# Sheet2.net
KiCad netlist of a schematic drawn in Altium Designer
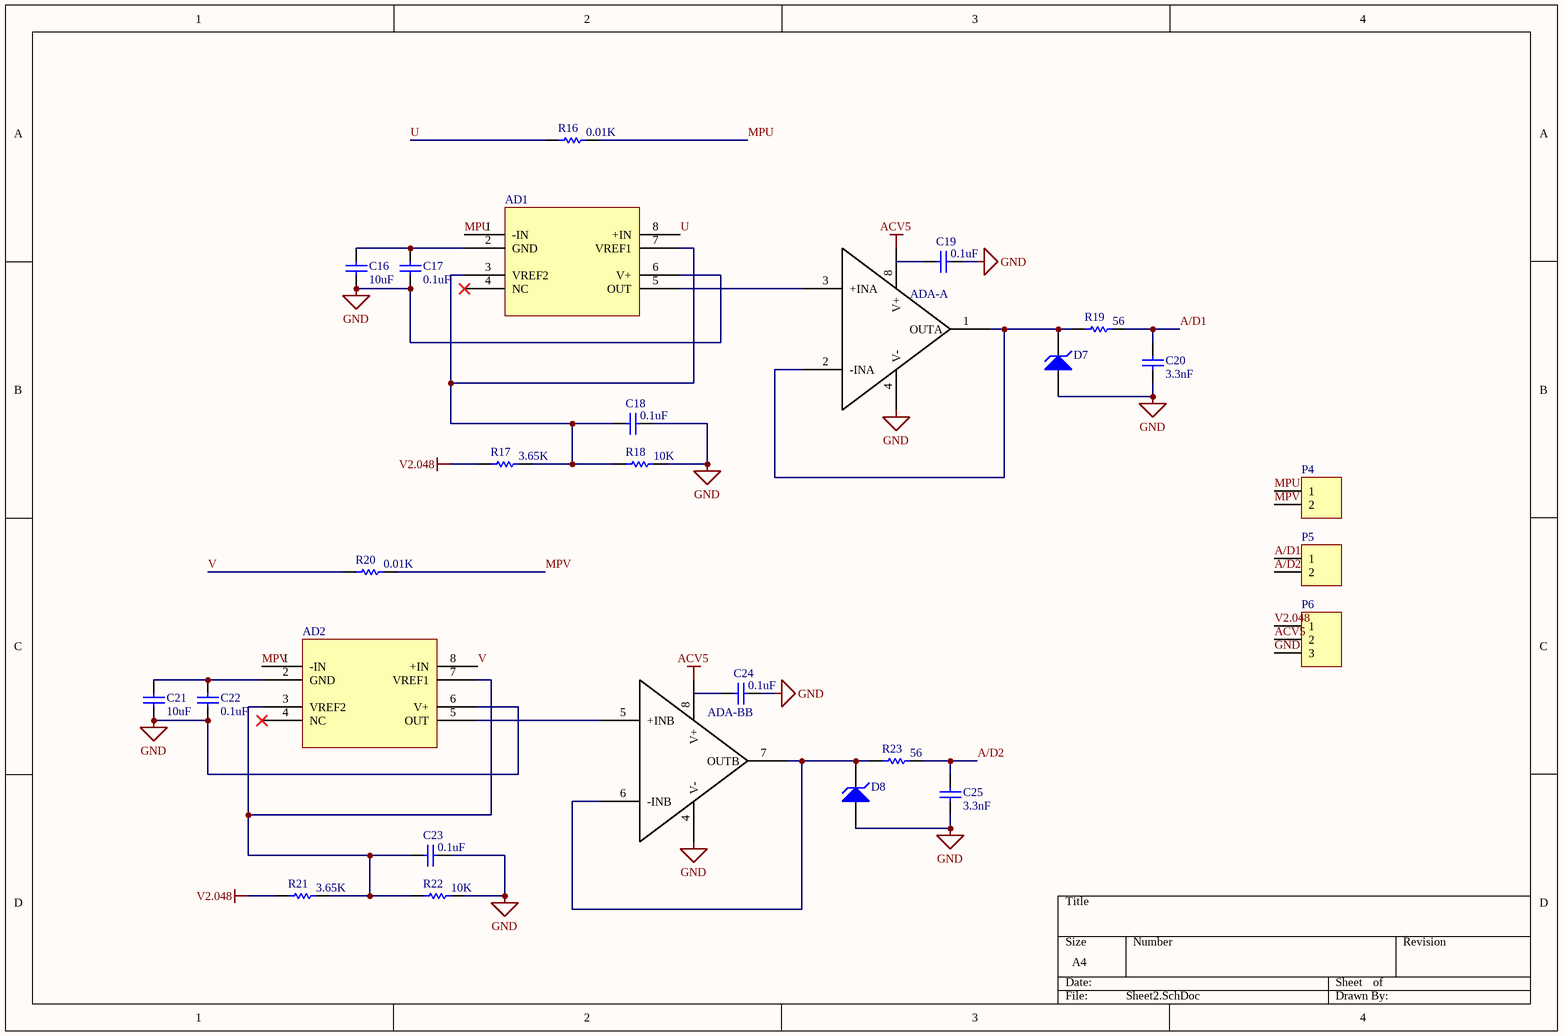
[diagram p0: Sheet2.SchDoc]

(export (version "E")
  (design (tool "Eeschema 10.0.6"))
  (components
    (comp (ref "AD1") (value "AD8210") (footprint "AD8210") (libsource (lib "AD8210") (part "Component_1")))
    (comp (ref "AD2") (value "AD8210") (footprint "AD8210") (libsource (lib "AD8210") (part "Component_1")))
    (comp (ref "ADA-")
      (value "Component_1")
      (footprint "ADA4096")
      (libsource (lib "ADA4096") (part "Component_1"))
    )
    (comp (ref "ADA-B")
      (value "ADA-B")
      (footprint "ADA4096")
      (libsource (lib "ADA4096") (part "Component_1"))
    )
    (comp (ref "C16")
      (value "10uF")
      (footprint "6-0805_M")
      (description "Capacitor")
      (fields (field (name "Comment") "Cap") (field (name "PUBLISHER") "Altium Limited"))
      (libsource (lib "Miscellaneous Devices") (part "Cap"))
    )
    (comp (ref "C17")
      (value "0.1uF")
      (footprint "6-0805_M")
      (description "Capacitor")
      (fields (field (name "Comment") "Cap") (field (name "PUBLISHER") "Altium Limited"))
      (libsource (lib "Miscellaneous Devices") (part "Cap"))
    )
    (comp (ref "C18")
      (value "0.1uF")
      (footprint "6-0805_M")
      (description "Capacitor")
      (fields (field (name "Comment") "Cap") (field (name "PUBLISHER") "Altium Limited"))
      (libsource (lib "Miscellaneous Devices") (part "Cap"))
    )
    (comp (ref "C19")
      (value "0.1uF")
      (footprint "6-0805_M")
      (description "Capacitor")
      (fields (field (name "Comment") "Cap") (field (name "PUBLISHER") "Altium Limited"))
      (libsource (lib "Miscellaneous Devices") (part "Cap"))
    )
    (comp (ref "C20")
      (value "3.3nF")
      (footprint "6-0805_M")
      (description "Capacitor")
      (fields (field (name "Comment") "Cap") (field (name "PUBLISHER") "Altium Limited"))
      (libsource (lib "Miscellaneous Devices") (part "Cap"))
    )
    (comp (ref "C21")
      (value "10uF")
      (footprint "6-0805_M")
      (description "Capacitor")
      (fields (field (name "Comment") "Cap") (field (name "PUBLISHER") "Altium Limited"))
      (libsource (lib "Miscellaneous Devices") (part "Cap"))
    )
    (comp (ref "C22")
      (value "0.1uF")
      (footprint "6-0805_M")
      (description "Capacitor")
      (fields (field (name "Comment") "Cap") (field (name "PUBLISHER") "Altium Limited"))
      (libsource (lib "Miscellaneous Devices") (part "Cap"))
    )
    (comp (ref "C23")
      (value "0.1uF")
      (footprint "6-0805_M")
      (description "Capacitor")
      (fields (field (name "Comment") "Cap") (field (name "PUBLISHER") "Altium Limited"))
      (libsource (lib "Miscellaneous Devices") (part "Cap"))
    )
    (comp (ref "C24")
      (value "0.1uF")
      (footprint "6-0805_M")
      (description "Capacitor")
      (fields (field (name "Comment") "Cap") (field (name "PUBLISHER") "Altium Limited"))
      (libsource (lib "Miscellaneous Devices") (part "Cap"))
    )
    (comp (ref "C25")
      (value "3.3nF")
      (footprint "6-0805_M")
      (description "Capacitor")
      (fields (field (name "Comment") "Cap") (field (name "PUBLISHER") "Altium Limited"))
      (libsource (lib "Miscellaneous Devices") (part "Cap"))
    )
    (comp (ref "D7")
      (value "D Zener")
      (footprint "12Z-2010")
      (description "Zener Diode")
      (fields (field (name "PUBLISHER") "Altium Limited"))
      (libsource (lib "Miscellaneous Devices") (part "D Zener"))
    )
    (comp (ref "D8")
      (value "D Zener")
      (footprint "12Z-2010")
      (description "Zener Diode")
      (fields (field (name "PUBLISHER") "Altium Limited"))
      (libsource (lib "Miscellaneous Devices") (part "D Zener"))
    )
    (comp (ref "P4")
      (value "Header 2")
      (footprint "HDR1X2")
      (description "Header, 2-Pin")
      (fields (field (name "PUBLISHER") "Altium Limited"))
      (libsource (lib "Miscellaneous Connectors") (part "Header 2"))
    )
    (comp (ref "P5")
      (value "Header 2")
      (footprint "HDR1X2")
      (description "Header, 2-Pin")
      (fields (field (name "PUBLISHER") "Altium Limited"))
      (libsource (lib "Miscellaneous Connectors") (part "Header 2"))
    )
    (comp (ref "P6")
      (value "Header 3")
      (footprint "HDR1X3")
      (description "Header, 3-Pin")
      (fields (field (name "PUBLISHER") "Altium Limited"))
      (libsource (lib "Miscellaneous Connectors") (part "Header 3"))
    )
    (comp (ref "R16")
      (value "0.01K")
      (footprint "6-0805_M")
      (description "Resistor")
      (fields (field (name "Comment") "Res1") (field (name "PUBLISHER") "Altium Limited"))
      (libsource (lib "Miscellaneous Devices") (part "Res1"))
    )
    (comp (ref "R17")
      (value "3.65K")
      (footprint "6-0805_M")
      (description "Resistor")
      (fields (field (name "Comment") "Res1") (field (name "PUBLISHER") "Altium Limited"))
      (libsource (lib "Miscellaneous Devices") (part "Res1"))
    )
    (comp (ref "R18")
      (value "10K")
      (footprint "6-0805_M")
      (description "Resistor")
      (fields (field (name "Comment") "Res1") (field (name "PUBLISHER") "Altium Limited"))
      (libsource (lib "Miscellaneous Devices") (part "Res1"))
    )
    (comp (ref "R19")
      (value "56")
      (footprint "6-0805_M")
      (description "Resistor")
      (fields (field (name "Comment") "Res1") (field (name "PUBLISHER") "Altium Limited"))
      (libsource (lib "Miscellaneous Devices") (part "Res1"))
    )
    (comp (ref "R20")
      (value "0.01K")
      (footprint "6-0805_M")
      (description "Resistor")
      (fields (field (name "Comment") "Res1") (field (name "PUBLISHER") "Altium Limited"))
      (libsource (lib "Miscellaneous Devices") (part "Res1"))
    )
    (comp (ref "R21")
      (value "3.65K")
      (footprint "6-0805_M")
      (description "Resistor")
      (fields (field (name "Comment") "Res1") (field (name "PUBLISHER") "Altium Limited"))
      (libsource (lib "Miscellaneous Devices") (part "Res1"))
    )
    (comp (ref "R22")
      (value "10K")
      (footprint "6-0805_M")
      (description "Resistor")
      (fields (field (name "Comment") "Res1") (field (name "PUBLISHER") "Altium Limited"))
      (libsource (lib "Miscellaneous Devices") (part "Res1"))
    )
    (comp (ref "R23")
      (value "56")
      (footprint "6-0805_M")
      (description "Resistor")
      (fields (field (name "Comment") "Res1") (field (name "PUBLISHER") "Altium Limited"))
      (libsource (lib "Miscellaneous Devices") (part "Res1"))
    )
  )
  (nets
    (net (code "1") (name "/A{slash}D1") (class "Default")
      (node (ref "C20") (pin "2") (pinfunction "2_2") (pintype "passive"))
      (node (ref "P5") (pin "1") (pinfunction "1_1") (pintype "passive"))
      (node (ref "R19") (pin "2") (pinfunction "2_2") (pintype "passive"))
    )
    (net (code "2") (name "/A{slash}D2") (class "Default")
      (node (ref "C25") (pin "2") (pinfunction "2_2") (pintype "passive"))
      (node (ref "P5") (pin "2") (pinfunction "2_2") (pintype "passive"))
      (node (ref "R23") (pin "2") (pinfunction "2_2") (pintype "passive"))
    )
    (net (code "3") (name "/MPU") (class "Default")
      (node (ref "AD1") (pin "1") (pinfunction "-IN_1") (pintype "passive"))
      (node (ref "P4") (pin "1") (pinfunction "1_1") (pintype "passive"))
      (node (ref "R16") (pin "2") (pinfunction "2_2") (pintype "passive"))
    )
    (net (code "4") (name "/MPV") (class "Default")
      (node (ref "AD2") (pin "1") (pinfunction "-IN_1") (pintype "passive"))
      (node (ref "P4") (pin "2") (pinfunction "2_2") (pintype "passive"))
      (node (ref "R20") (pin "2") (pinfunction "2_2") (pintype "passive"))
    )
    (net (code "5") (name "/U") (class "Default")
      (node (ref "AD1") (pin "8") (pinfunction "+IN_8") (pintype "passive"))
      (node (ref "R16") (pin "1") (pinfunction "1_1") (pintype "passive"))
    )
    (net (code "6") (name "/V") (class "Default")
      (node (ref "AD2") (pin "8") (pinfunction "+IN_8") (pintype "passive"))
      (node (ref "R20") (pin "1") (pinfunction "1_1") (pintype "passive"))
    )
    (net (code "7") (name "ACV5") (class "Default")
      (node (ref "ADA-") (pin "8") (pinfunction "V+_8") (pintype "passive"))
      (node (ref "ADA-B") (pin "8") (pinfunction "V+_8") (pintype "passive"))
      (node (ref "P6") (pin "2") (pinfunction "2_2") (pintype "passive"))
    )
    (net (code "8") (name "GND") (class "Default")
      (node (ref "AD1") (pin "6") (pinfunction "V+_6") (pintype "passive"))
      (node (ref "AD2") (pin "6") (pinfunction "V+_6") (pintype "passive"))
      (node (ref "ADA-") (pin "4") (pinfunction "V-_4") (pintype "passive"))
      (node (ref "ADA-B") (pin "4") (pinfunction "V-_4") (pintype "passive"))
      (node (ref "C16") (pin "1") (pinfunction "1_1") (pintype "passive"))
      (node (ref "C17") (pin "1") (pinfunction "1_1") (pintype "passive"))
      (node (ref "C18") (pin "2") (pinfunction "2_2") (pintype "passive"))
      (node (ref "C19") (pin "2") (pinfunction "2_2") (pintype "passive"))
      (node (ref "C20") (pin "1") (pinfunction "1_1") (pintype "passive"))
      (node (ref "C21") (pin "1") (pinfunction "1_1") (pintype "passive"))
      (node (ref "C22") (pin "1") (pinfunction "1_1") (pintype "passive"))
      (node (ref "C23") (pin "2") (pinfunction "2_2") (pintype "passive"))
      (node (ref "C24") (pin "2") (pinfunction "2_2") (pintype "passive"))
      (node (ref "C25") (pin "1") (pinfunction "1_1") (pintype "passive"))
      (node (ref "D7") (pin "1") (pinfunction "A_1") (pintype "passive"))
      (node (ref "D8") (pin "1") (pinfunction "A_1") (pintype "passive"))
      (node (ref "P6") (pin "3") (pinfunction "3_3") (pintype "passive"))
      (node (ref "R18") (pin "2") (pinfunction "2_2") (pintype "passive"))
      (node (ref "R22") (pin "2") (pinfunction "2_2") (pintype "passive"))
    )
    (net (code "9") (name "Net-(AD1-GND)") (class "Default")
      (node (ref "AD1") (pin "2") (pinfunction "GND_2") (pintype "passive"))
      (node (ref "C16") (pin "2") (pinfunction "2_2") (pintype "passive"))
      (node (ref "C17") (pin "2") (pinfunction "2_2") (pintype "passive"))
    )
    (net (code "10") (name "Net-(AD1-OUT)") (class "Default")
      (node (ref "AD1") (pin "5") (pinfunction "OUT_5") (pintype "passive"))
      (node (ref "ADA-") (pin "3") (pinfunction "+INA_3") (pintype "passive"))
    )
    (net (code "11") (name "Net-(AD1-VREF1)") (class "Default")
      (node (ref "AD1") (pin "3") (pinfunction "VREF2_3") (pintype "passive"))
      (node (ref "AD1") (pin "7") (pinfunction "VREF1_7") (pintype "passive"))
      (node (ref "C18") (pin "1") (pinfunction "1_1") (pintype "passive"))
      (node (ref "R17") (pin "2") (pinfunction "2_2") (pintype "passive"))
      (node (ref "R18") (pin "1") (pinfunction "1_1") (pintype "passive"))
    )
    (net (code "12") (name "Net-(AD2-GND)") (class "Default")
      (node (ref "AD2") (pin "2") (pinfunction "GND_2") (pintype "passive"))
      (node (ref "C21") (pin "2") (pinfunction "2_2") (pintype "passive"))
      (node (ref "C22") (pin "2") (pinfunction "2_2") (pintype "passive"))
    )
    (net (code "13") (name "Net-(AD2-OUT)") (class "Default")
      (node (ref "AD2") (pin "5") (pinfunction "OUT_5") (pintype "passive"))
      (node (ref "ADA-B") (pin "5") (pinfunction "+INB_5") (pintype "passive"))
    )
    (net (code "14") (name "Net-(AD2-VREF1)") (class "Default")
      (node (ref "AD2") (pin "3") (pinfunction "VREF2_3") (pintype "passive"))
      (node (ref "AD2") (pin "7") (pinfunction "VREF1_7") (pintype "passive"))
      (node (ref "C23") (pin "1") (pinfunction "1_1") (pintype "passive"))
      (node (ref "R21") (pin "2") (pinfunction "2_2") (pintype "passive"))
      (node (ref "R22") (pin "1") (pinfunction "1_1") (pintype "passive"))
    )
    (net (code "15") (name "Net-(ADA-A--INA)") (class "Default")
      (node (ref "ADA-") (pin "1") (pinfunction "OUTA_1") (pintype "passive"))
      (node (ref "ADA-") (pin "2") (pinfunction "-INA_2") (pintype "passive"))
      (node (ref "D7") (pin "2") (pinfunction "K_2") (pintype "passive"))
      (node (ref "R19") (pin "1") (pinfunction "1_1") (pintype "passive"))
    )
    (net (code "16") (name "Net-(ADA-BB--INB)") (class "Default")
      (node (ref "ADA-B") (pin "6") (pinfunction "-INB_6") (pintype "passive"))
      (node (ref "ADA-B") (pin "7") (pinfunction "OUTB_7") (pintype "passive"))
      (node (ref "D8") (pin "2") (pinfunction "K_2") (pintype "passive"))
      (node (ref "R23") (pin "1") (pinfunction "1_1") (pintype "passive"))
    )
    (net (code "17") (name "V2.048") (class "Default")
      (node (ref "P6") (pin "1") (pinfunction "1_1") (pintype "passive"))
      (node (ref "R17") (pin "1") (pinfunction "1_1") (pintype "passive"))
      (node (ref "R21") (pin "1") (pinfunction "1_1") (pintype "passive"))
    )
    (net (code "18") (name "unconnected-(AD1-NC-Pad4)") (class "Default")
      (node (ref "AD1") (pin "4") (pinfunction "NC_4") (pintype "passive+no_connect"))
    )
    (net (code "19") (name "unconnected-(AD2-NC-Pad4)") (class "Default")
      (node (ref "AD2") (pin "4") (pinfunction "NC_4") (pintype "passive+no_connect"))
    )
    (net (code "20") (name "unconnected-(C19-Pad1)") (class "Default")
      (node (ref "C19") (pin "1") (pinfunction "1_1") (pintype "passive"))
    )
    (net (code "21") (name "unconnected-(C24-Pad1)") (class "Default")
      (node (ref "C24") (pin "1") (pinfunction "1_1") (pintype "passive"))
    )
  )
)
